# Communication.net
KiCad netlist of a schematic drawn in Altium Designer
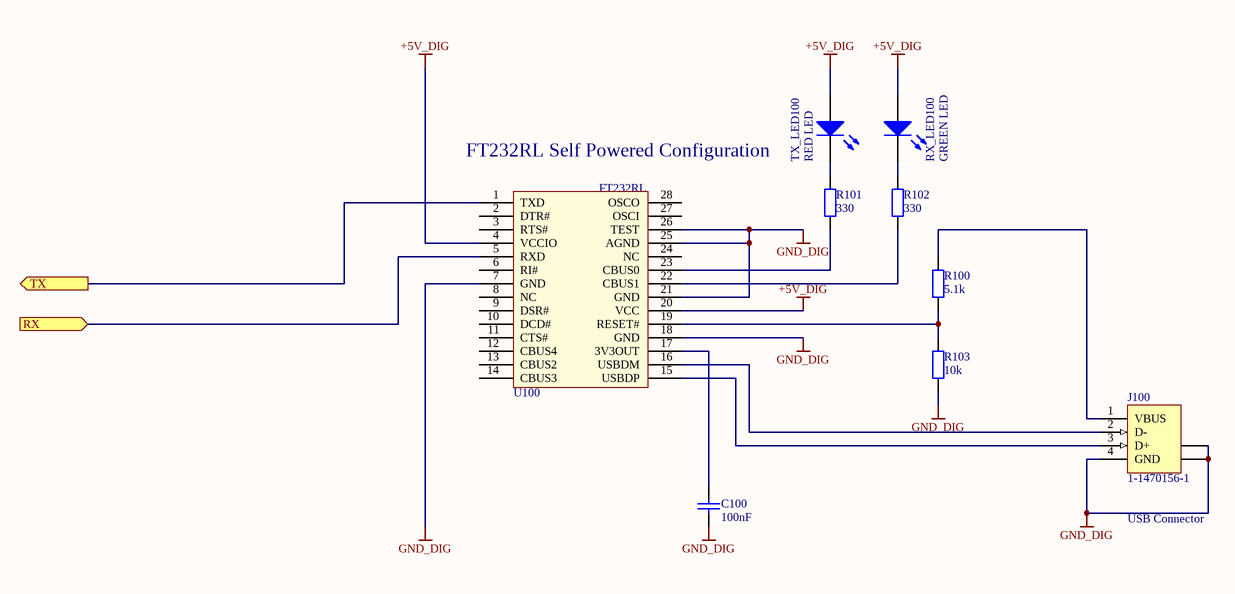
[diagram p0: Communication.SchDoc]

(export (version "E")
  (design (tool "Eeschema 10.0.6"))
  (components
    (comp (ref "C100")
      (value "100nF")
      (footprint "3216[1206]")
      (fields (field (name "Comment") "Cap"))
      (libsource (lib "Capacitors") (part "Cap"))
    )
    (comp (ref "J100")
      (value "1-1470156-1")
      (footprint "USB2.5-2H4D")
      (description "USB 1.1, Right Angle, Thru-Hole, B Type, Receptacle, 4 Position, White")
      (fields (field (name "PUBLISHER") "Altium Limited"))
      (libsource (lib "AMP Serial Bus USB") (part "1-1470156-1"))
    )
    (comp (ref "R100")
      (value "5.1k")
      (footprint "3216[1206]")
      (fields (field (name "Comment") "Resistor"))
      (libsource (lib "Resistor") (part "RES1"))
    )
    (comp (ref "R101")
      (value "330")
      (footprint "3216[1206]")
      (fields (field (name "Comment") "Resistor"))
      (libsource (lib "Resistor") (part "RES1"))
    )
    (comp (ref "R102")
      (value "330")
      (footprint "3216[1206]")
      (fields (field (name "Comment") "Resistor"))
      (libsource (lib "Resistor") (part "RES1"))
    )
    (comp (ref "R103")
      (value "10k")
      (footprint "3216[1206]")
      (fields (field (name "Comment") "Resistor"))
      (libsource (lib "Resistor") (part "RES1"))
    )
    (comp (ref "RX_LED100") (value "GREEN LED") (footprint "LED_1206") (libsource (lib "LED") (part "LED")))
    (comp (ref "TX_LED100") (value "RED LED") (footprint "LED_1206") (libsource (lib "LED") (part "LED")))
    (comp (ref "U100") (value "FT232RL") (footprint "SSOP28") (libsource (lib "COMM") (part "FT232RL")))
  )
  (nets
    (net (code "1") (name "+5V_DIG") (class "Default")
      (node (ref "RX_LED100") (pin "A") (pinfunction "A_A") (pintype "passive"))
      (node (ref "TX_LED100") (pin "A") (pinfunction "A_A") (pintype "passive"))
      (node (ref "U100") (pin "20") (pinfunction "VCC_20") (pintype "passive"))
      (node (ref "U100") (pin "4") (pinfunction "VCCIO_4") (pintype "passive"))
    )
    (net (code "2") (name "/RX") (class "Default")
      (node (ref "U100") (pin "5") (pinfunction "RXD_5") (pintype "passive"))
    )
    (net (code "3") (name "/TX") (class "Default")
      (node (ref "U100") (pin "1") (pinfunction "TXD_1") (pintype "passive"))
    )
    (net (code "4") (name "GND_DIG") (class "Default")
      (node (ref "C100") (pin "1") (pinfunction "1_1") (pintype "passive"))
      (node (ref "J100") (pin "4") (pinfunction "GND_4") (pintype "power_in"))
      (node (ref "J100") (pin "5") (pinfunction "SHLD_5") (pintype "passive"))
      (node (ref "J100") (pin "6") (pinfunction "SHLD_6") (pintype "passive"))
      (node (ref "R103") (pin "1") (pinfunction "1_1") (pintype "passive"))
      (node (ref "U100") (pin "18") (pinfunction "GND_18") (pintype "passive"))
      (node (ref "U100") (pin "21") (pinfunction "GND_21") (pintype "passive"))
      (node (ref "U100") (pin "25") (pinfunction "AGND_25") (pintype "passive"))
      (node (ref "U100") (pin "26") (pinfunction "TEST_26") (pintype "passive"))
      (node (ref "U100") (pin "7") (pinfunction "GND_7") (pintype "passive"))
    )
    (net (code "5") (name "Net-(J100-D+)") (class "Default")
      (node (ref "J100") (pin "3") (pinfunction "D+_3") (pintype "input"))
      (node (ref "U100") (pin "15") (pinfunction "USBDP_15") (pintype "passive"))
    )
    (net (code "6") (name "Net-(J100-D-)") (class "Default")
      (node (ref "J100") (pin "2") (pinfunction "D-_2") (pintype "input"))
      (node (ref "U100") (pin "16") (pinfunction "USBDM_16") (pintype "passive"))
    )
    (net (code "7") (name "Net-(J100-VBUS)") (class "Default")
      (node (ref "J100") (pin "1") (pinfunction "VBUS_1") (pintype "power_in"))
      (node (ref "R100") (pin "2") (pinfunction "2_2") (pintype "passive"))
    )
    (net (code "8") (name "Net-(R101-Pad2)") (class "Default")
      (node (ref "R101") (pin "2") (pinfunction "2_2") (pintype "passive"))
      (node (ref "TX_LED100") (pin "K") (pinfunction "K_K") (pintype "passive"))
    )
    (net (code "9") (name "Net-(R102-Pad2)") (class "Default")
      (node (ref "R102") (pin "2") (pinfunction "2_2") (pintype "passive"))
      (node (ref "RX_LED100") (pin "K") (pinfunction "K_K") (pintype "passive"))
    )
    (net (code "10") (name "Net-(U100-3V3OUT)") (class "Default")
      (node (ref "C100") (pin "2") (pinfunction "2_2") (pintype "passive"))
      (node (ref "U100") (pin "17") (pinfunction "3V3OUT_17") (pintype "passive"))
    )
    (net (code "11") (name "Net-(U100-CBUS0)") (class "Default")
      (node (ref "R101") (pin "1") (pinfunction "1_1") (pintype "passive"))
      (node (ref "U100") (pin "23") (pinfunction "CBUS0_23") (pintype "passive"))
    )
    (net (code "12") (name "Net-(U100-CBUS1)") (class "Default")
      (node (ref "R102") (pin "1") (pinfunction "1_1") (pintype "passive"))
      (node (ref "U100") (pin "22") (pinfunction "CBUS1_22") (pintype "passive"))
    )
    (net (code "13") (name "Net-(U100-RESET#)") (class "Default")
      (node (ref "R100") (pin "1") (pinfunction "1_1") (pintype "passive"))
      (node (ref "R103") (pin "2") (pinfunction "2_2") (pintype "passive"))
      (node (ref "U100") (pin "19") (pinfunction "RESET#_19") (pintype "passive"))
    )
    (net (code "14") (name "unconnected-(U100-CBUS2-Pad13)") (class "Default")
      (node (ref "U100") (pin "13") (pinfunction "CBUS2_13") (pintype "passive"))
    )
    (net (code "15") (name "unconnected-(U100-CBUS3-Pad14)") (class "Default")
      (node (ref "U100") (pin "14") (pinfunction "CBUS3_14") (pintype "passive"))
    )
    (net (code "16") (name "unconnected-(U100-CBUS4-Pad12)") (class "Default")
      (node (ref "U100") (pin "12") (pinfunction "CBUS4_12") (pintype "passive"))
    )
    (net (code "17") (name "unconnected-(U100-CTS#-Pad11)") (class "Default")
      (node (ref "U100") (pin "11") (pinfunction "CTS#_11") (pintype "passive"))
    )
    (net (code "18") (name "unconnected-(U100-DCD#-Pad10)") (class "Default")
      (node (ref "U100") (pin "10") (pinfunction "DCD#_10") (pintype "passive"))
    )
    (net (code "19") (name "unconnected-(U100-DSR#-Pad9)") (class "Default")
      (node (ref "U100") (pin "9") (pinfunction "DSR#_9") (pintype "passive"))
    )
    (net (code "20") (name "unconnected-(U100-DTR#-Pad2)") (class "Default")
      (node (ref "U100") (pin "2") (pinfunction "DTR#_2") (pintype "passive"))
    )
    (net (code "21") (name "unconnected-(U100-NC-Pad8)") (class "Default")
      (node (ref "U100") (pin "8") (pinfunction "NC_8") (pintype "passive"))
    )
    (net (code "22") (name "unconnected-(U100-NC-Pad24)") (class "Default")
      (node (ref "U100") (pin "24") (pinfunction "NC_24") (pintype "passive"))
    )
    (net (code "23") (name "unconnected-(U100-OSCI-Pad27)") (class "Default")
      (node (ref "U100") (pin "27") (pinfunction "OSCI_27") (pintype "passive"))
    )
    (net (code "24") (name "unconnected-(U100-OSCO-Pad28)") (class "Default")
      (node (ref "U100") (pin "28") (pinfunction "OSCO_28") (pintype "passive"))
    )
    (net (code "25") (name "unconnected-(U100-RI#-Pad6)") (class "Default")
      (node (ref "U100") (pin "6") (pinfunction "RI#_6") (pintype "passive"))
    )
    (net (code "26") (name "unconnected-(U100-RTS#-Pad3)") (class "Default")
      (node (ref "U100") (pin "3") (pinfunction "RTS#_3") (pintype "passive"))
    )
  )
)
